# RePico.net
KiCad netlist of a schematic drawn in EAGLE
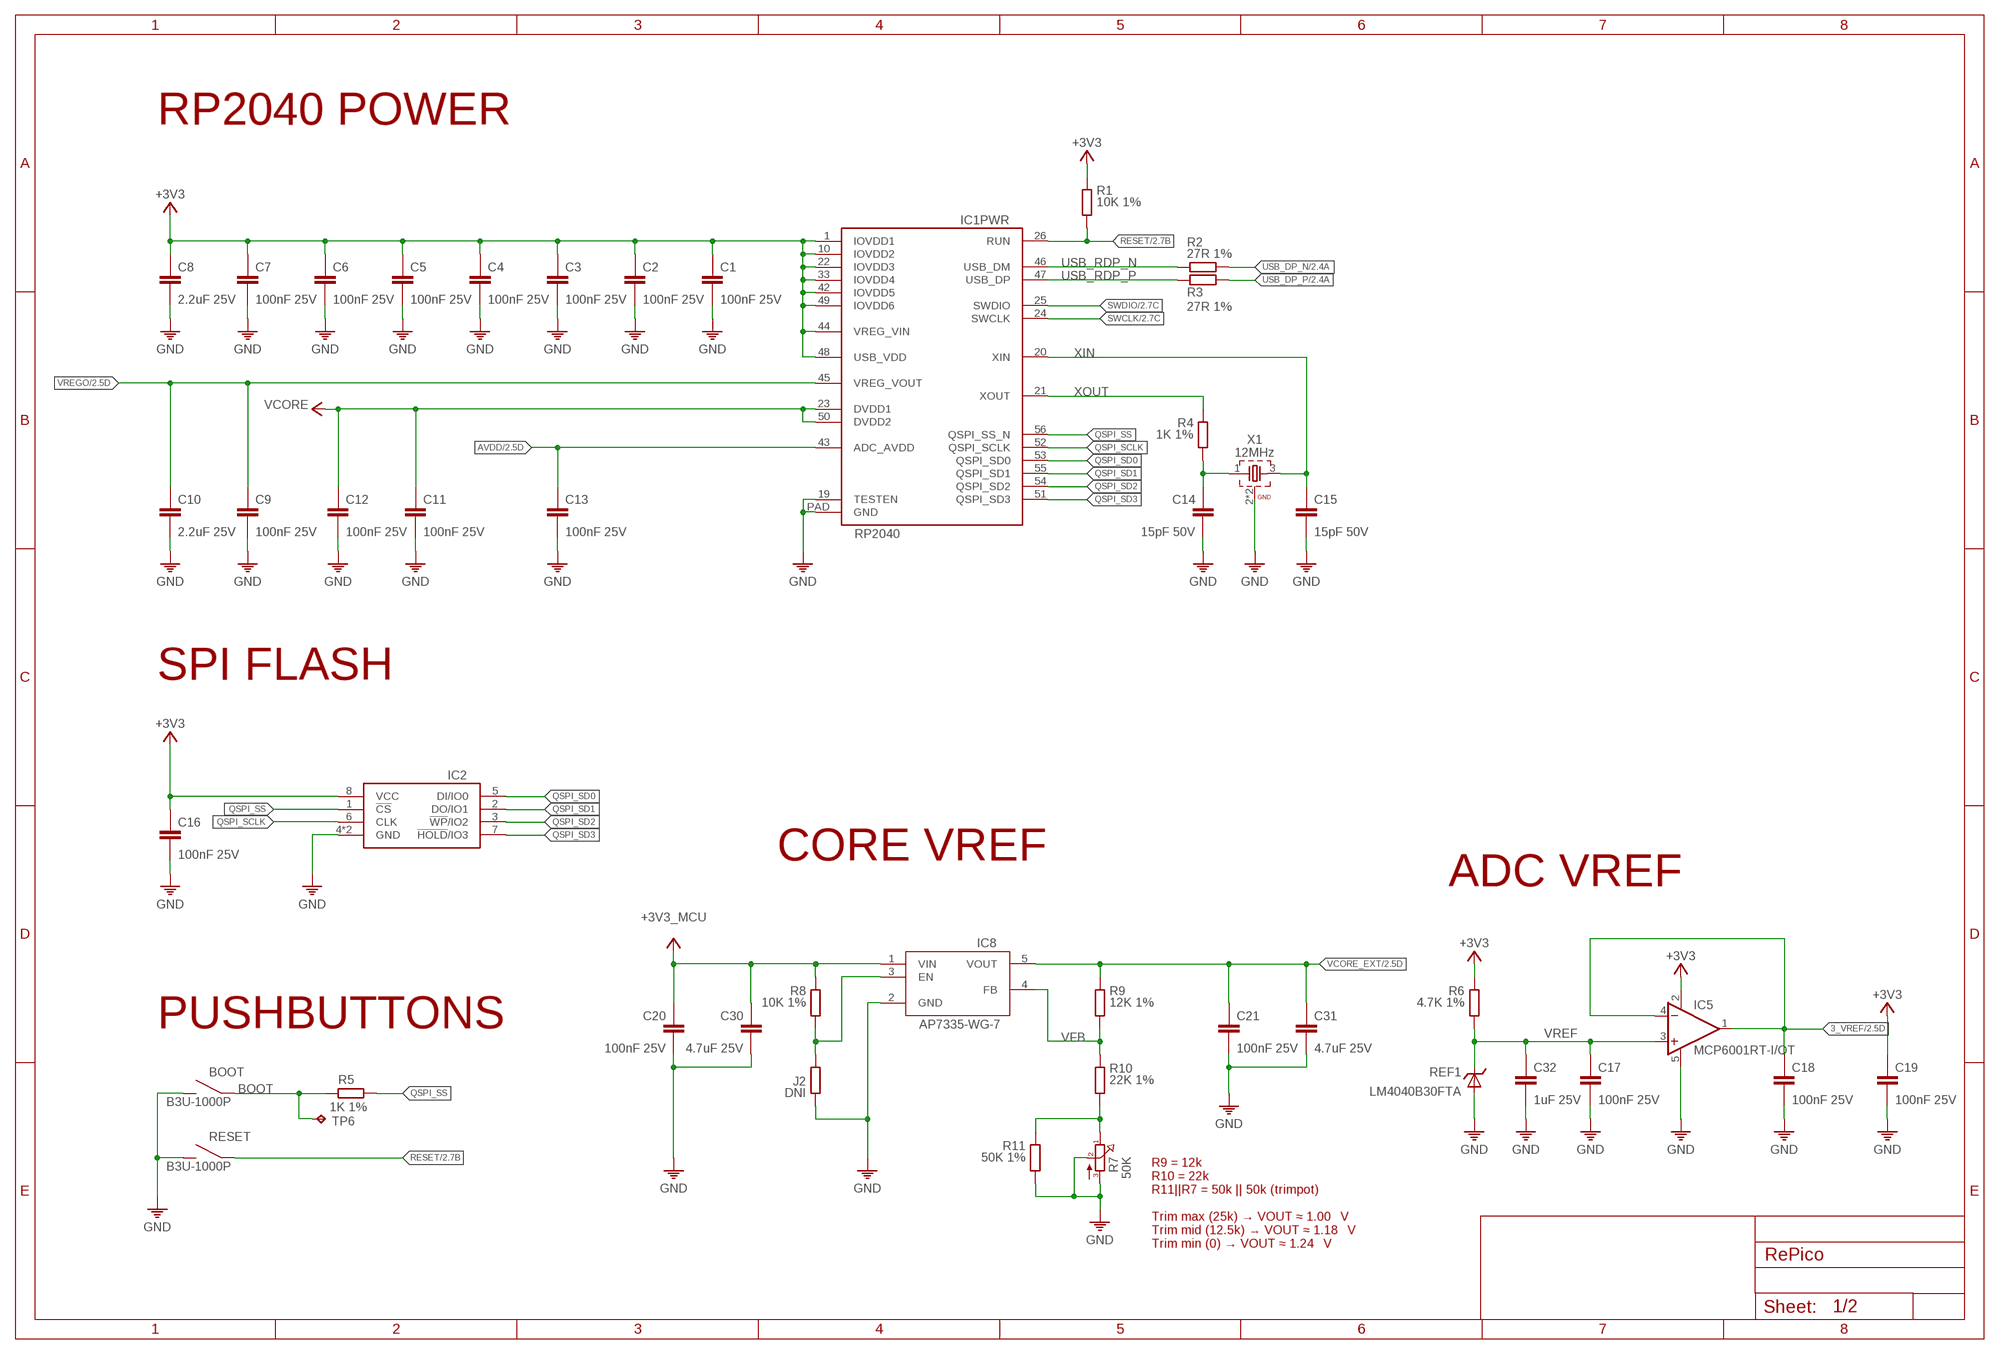
[diagram p0: schematic, sheet 1]
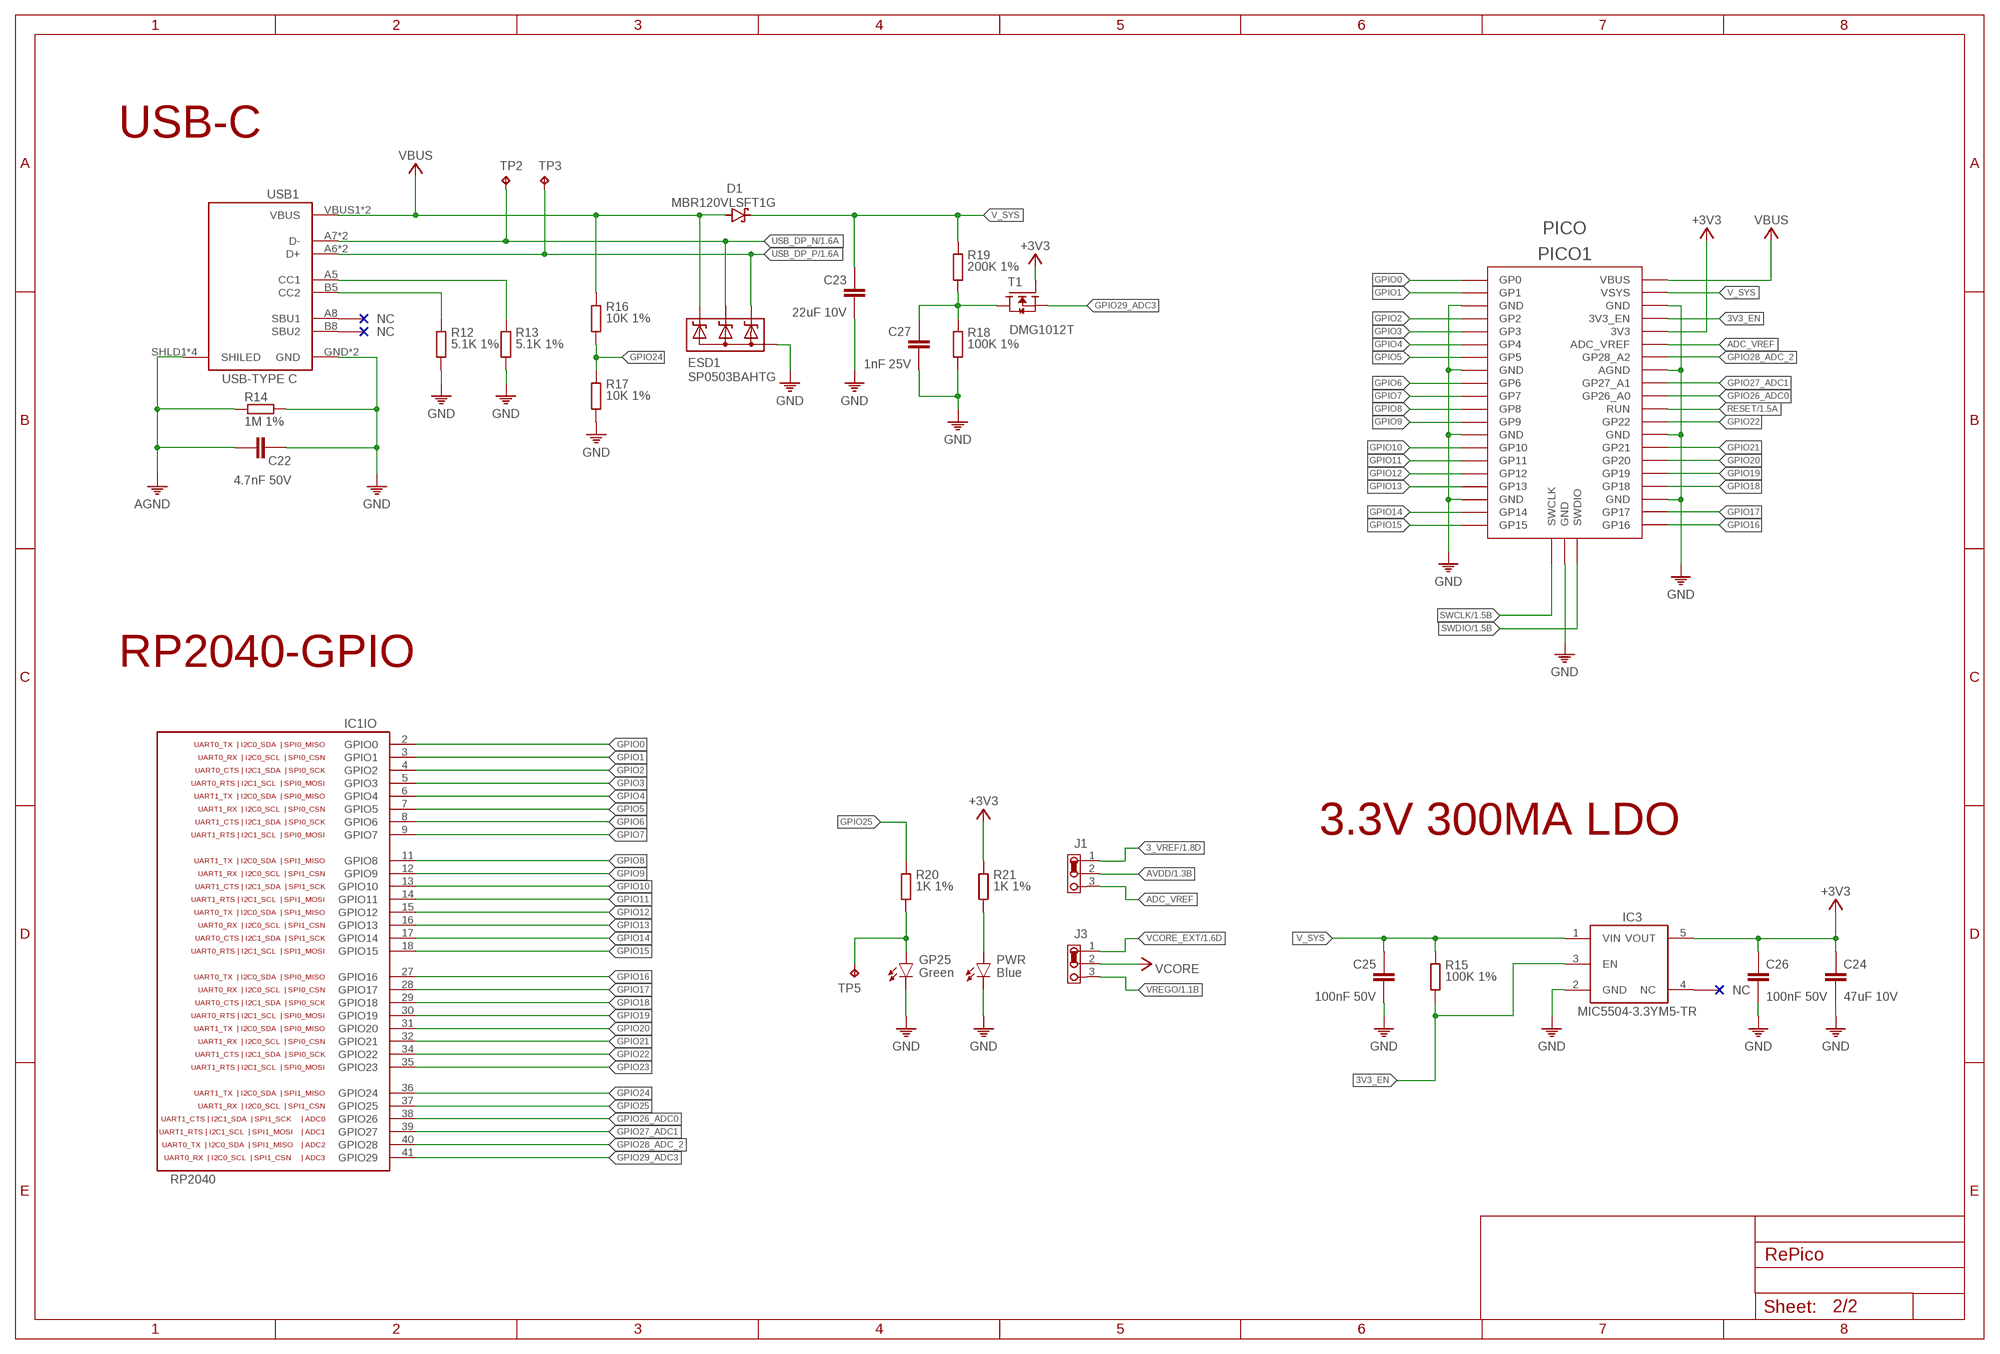
[diagram p1: schematic, sheet 2]

(export (version "E")
  (design (tool "Eeschema 10.0.6"))
  (components
    (comp (ref "BOOT")
      (value "B3U-1000P")
      (footprint "eagle-import:B3U-1000P")
      (fields (field (name "LCSC_PART") "C231329"))
      (libsource (lib "eagle-import") (part "B3U-1000P"))
    )
    (comp (ref "C1")
      (value "100nF 25V")
      (footprint "eagle-import:0201")
      (fields (field (name "LCSC_PART") "C76939"))
      (libsource (lib "eagle-import") (part "100NF-25V-0201"))
    )
    (comp (ref "C2")
      (value "100nF 25V")
      (footprint "eagle-import:0201")
      (fields (field (name "LCSC_PART") "C76939"))
      (libsource (lib "eagle-import") (part "100NF-25V-0201"))
    )
    (comp (ref "C3")
      (value "100nF 25V")
      (footprint "eagle-import:0201")
      (fields (field (name "LCSC_PART") "C76939"))
      (libsource (lib "eagle-import") (part "100NF-25V-0201"))
    )
    (comp (ref "C4")
      (value "100nF 25V")
      (footprint "eagle-import:0201")
      (fields (field (name "LCSC_PART") "C76939"))
      (libsource (lib "eagle-import") (part "100NF-25V-0201"))
    )
    (comp (ref "C5")
      (value "100nF 25V")
      (footprint "eagle-import:0201")
      (fields (field (name "LCSC_PART") "C76939"))
      (libsource (lib "eagle-import") (part "100NF-25V-0201"))
    )
    (comp (ref "C6")
      (value "100nF 25V")
      (footprint "eagle-import:0201")
      (fields (field (name "LCSC_PART") "C76939"))
      (libsource (lib "eagle-import") (part "100NF-25V-0201"))
    )
    (comp (ref "C7")
      (value "100nF 25V")
      (footprint "eagle-import:0201")
      (fields (field (name "LCSC_PART") "C76939"))
      (libsource (lib "eagle-import") (part "100NF-25V-0201"))
    )
    (comp (ref "C8")
      (value "2.2uF 25V")
      (footprint "eagle-import:0402")
      (fields (field (name "LCSC_PART") "C385032"))
      (libsource (lib "eagle-import") (part "2.2UF-25V0402"))
    )
    (comp (ref "C9")
      (value "100nF 25V")
      (footprint "eagle-import:0201")
      (fields (field (name "LCSC_PART") "C76939"))
      (libsource (lib "eagle-import") (part "100NF-25V-0201"))
    )
    (comp (ref "C10")
      (value "2.2uF 25V")
      (footprint "eagle-import:0402")
      (fields (field (name "LCSC_PART") "C385032"))
      (libsource (lib "eagle-import") (part "2.2UF-25V0402"))
    )
    (comp (ref "C11")
      (value "100nF 25V")
      (footprint "eagle-import:0201")
      (fields (field (name "LCSC_PART") "C76939"))
      (libsource (lib "eagle-import") (part "100NF-25V-0201"))
    )
    (comp (ref "C12")
      (value "100nF 25V")
      (footprint "eagle-import:0201")
      (fields (field (name "LCSC_PART") "C76939"))
      (libsource (lib "eagle-import") (part "100NF-25V-0201"))
    )
    (comp (ref "C13")
      (value "100nF 25V")
      (footprint "eagle-import:0201")
      (fields (field (name "LCSC_PART") "C76939"))
      (libsource (lib "eagle-import") (part "100NF-25V-0201"))
    )
    (comp (ref "C14")
      (value "15pF 50V")
      (footprint "eagle-import:0201")
      (fields (field (name "LCSC_PART") "C22374851"))
      (libsource (lib "eagle-import") (part "15PF-50V0201"))
    )
    (comp (ref "C15")
      (value "15pF 50V")
      (footprint "eagle-import:0201")
      (fields (field (name "LCSC_PART") "C22374851"))
      (libsource (lib "eagle-import") (part "15PF-50V0201"))
    )
    (comp (ref "C16")
      (value "100nF 25V")
      (footprint "eagle-import:0201")
      (fields (field (name "LCSC_PART") "C76939"))
      (libsource (lib "eagle-import") (part "100NF-25V-0201"))
    )
    (comp (ref "C17")
      (value "100nF 25V")
      (footprint "eagle-import:0201")
      (fields (field (name "LCSC_PART") "C76939"))
      (libsource (lib "eagle-import") (part "100NF-25V-0201"))
    )
    (comp (ref "C18")
      (value "100nF 25V")
      (footprint "eagle-import:0201")
      (fields (field (name "LCSC_PART") "C76939"))
      (libsource (lib "eagle-import") (part "100NF-25V-0201"))
    )
    (comp (ref "C19")
      (value "100nF 25V")
      (footprint "eagle-import:0201")
      (fields (field (name "LCSC_PART") "C76939"))
      (libsource (lib "eagle-import") (part "100NF-25V-0201"))
    )
    (comp (ref "C20")
      (value "100nF 25V")
      (footprint "eagle-import:0201")
      (fields (field (name "LCSC_PART") "C76939"))
      (libsource (lib "eagle-import") (part "100NF-25V-0201"))
    )
    (comp (ref "C21")
      (value "100nF 25V")
      (footprint "eagle-import:0201")
      (fields (field (name "LCSC_PART") "C76939"))
      (libsource (lib "eagle-import") (part "100NF-25V-0201"))
    )
    (comp (ref "C30")
      (value "4.7uF 25V")
      (footprint "eagle-import:0402")
      (fields (field (name "LCSC_PART") "C22367824"))
      (libsource (lib "eagle-import") (part "4.7UF-25V0402"))
    )
    (comp (ref "C31")
      (value "4.7uF 25V")
      (footprint "eagle-import:0402")
      (fields (field (name "LCSC_PART") "C22367824"))
      (libsource (lib "eagle-import") (part "4.7UF-25V0402"))
    )
    (comp (ref "C32")
      (value "1uF 25V")
      (footprint "eagle-import:0402")
      (fields (field (name "LCSC_PART") "C52923"))
      (libsource (lib "eagle-import") (part "1UF-25V0402"))
    )
    (comp (ref "IC1")
      (value "RP2040")
      (footprint "eagle-import:QFN56")
      (fields (field (name "LCSC_PART") "C2040"))
      (libsource (lib "eagle-import") (part "RP-2040"))
    )
    (comp (ref "IC2")
      (value "W25Q128JVP")
      (footprint "eagle-import:SON127P600X500X75-8N")
      (libsource (lib "eagle-import") (part "W25Q128JVP"))
    )
    (comp (ref "IC5")
      (value "MCP6001RT-I/OT")
      (footprint "eagle-import:SOT23-5")
      (fields (field (name "LCSC_PART") "C154973"))
      (libsource (lib "eagle-import") (part "MCP6001RT"))
    )
    (comp (ref "IC8")
      (value "AP7335-WG-7")
      (footprint "eagle-import:SOT23-5")
      (fields (field (name "LCSC_PART") "C460382"))
      (libsource (lib "eagle-import") (part "AP7335-WG-7"))
    )
    (comp (ref "J2")
      (value "DNI")
      (footprint "eagle-import:R0201")
      (libsource (lib "eagle-import") (part "R0201"))
    )
    (comp (ref "R1")
      (value "10K 1%")
      (footprint "eagle-import:0201")
      (fields (field (name "LCSC_PART") "C473048"))
      (libsource (lib "eagle-import") (part "10K-1%0201"))
    )
    (comp (ref "R2")
      (value "27R 1%")
      (footprint "eagle-import:0201")
      (fields (field (name "LCSC_PART") "C473051"))
      (libsource (lib "eagle-import") (part "27R-1%0201"))
    )
    (comp (ref "R3")
      (value "27R 1%")
      (footprint "eagle-import:0201")
      (fields (field (name "LCSC_PART") "C473051"))
      (libsource (lib "eagle-import") (part "27R-1%0201"))
    )
    (comp (ref "R4")
      (value "1K 1%")
      (footprint "eagle-import:0201")
      (fields (field (name "LCSC_PART") "C270365"))
      (libsource (lib "eagle-import") (part "1K-1%0201"))
    )
    (comp (ref "R5")
      (value "1K 1%")
      (footprint "eagle-import:0201")
      (fields (field (name "LCSC_PART") "C270365"))
      (libsource (lib "eagle-import") (part "1K-1%0201"))
    )
    (comp (ref "R6")
      (value "4.7K 1%")
      (footprint "eagle-import:0402")
      (fields (field (name "LCSC_PART") "C25900"))
      (libsource (lib "eagle-import") (part "4.7K-1%0402"))
    )
    (comp (ref "R7")
      (value "50K")
      (footprint "eagle-import:SMD_TRIMM")
      (fields (field (name "LCSC_PART") "C913246"))
      (libsource (lib "eagle-import") (part "TRIM-3X3.6-TC33X-2-503E"))
    )
    (comp (ref "R8")
      (value "10K 1%")
      (footprint "eagle-import:0201")
      (fields (field (name "LCSC_PART") "C473048"))
      (libsource (lib "eagle-import") (part "10K-1%0201"))
    )
    (comp (ref "R9")
      (value "12K 1%")
      (footprint "eagle-import:0201")
      (fields (field (name "LCSC_PART") "C270363"))
      (libsource (lib "eagle-import") (part "12K-1%0201"))
    )
    (comp (ref "R10")
      (value "22K 1%")
      (footprint "eagle-import:0201")
      (fields (field (name "LCSC_PART") "C474416"))
      (libsource (lib "eagle-import") (part "22K-1%0201"))
    )
    (comp (ref "R11")
      (value "50K 1%")
      (footprint "eagle-import:0402")
      (fields (field (name "LCSC_PART") "C166559"))
      (libsource (lib "eagle-import") (part "50K-1%0402"))
    )
    (comp (ref "REF1")
      (value "LM4040B30FTA")
      (footprint "eagle-import:SOT23")
      (fields (field (name "LCSC_PART") "C460604"))
      (libsource (lib "eagle-import") (part "LM4040BXX"))
    )
    (comp (ref "RESET")
      (value "B3U-1000P")
      (footprint "eagle-import:B3U-1000P")
      (fields (field (name "LCSC_PART") "C231329"))
      (libsource (lib "eagle-import") (part "B3U-1000P"))
    )
    (comp (ref "TP6")
      (value "TPB1,27")
      (footprint "eagle-import:B1,27")
      (libsource (lib "eagle-import") (part "TPB1,27"))
    )
    (comp (ref "X1")
      (value "12MHz")
      (footprint "eagle-import:WE-XTAL_CFPX-180")
      (fields (field (name "LCSC_PART") "C9002"))
      (libsource (lib "eagle-import") (part "CRYSTAL-3225X322512MSB4SI"))
    )
    (comp (ref "C22")
      (value "4.7nF 50V")
      (footprint "eagle-import:0603")
      (fields (field (name "LCSC_PART") "C53987"))
      (libsource (lib "eagle-import") (part "4.7NF-50V0603"))
    )
    (comp (ref "C23")
      (value "22uF 10V")
      (footprint "eagle-import:0603")
      (fields (field (name "LCSC_PART") "C60077"))
      (libsource (lib "eagle-import") (part "22UF-10V-0603"))
    )
    (comp (ref "C24")
      (value "47uF 10V")
      (footprint "eagle-import:0805")
      (fields (field (name "LCSC_PART") "C6119904"))
      (libsource (lib "eagle-import") (part "47UF-10V0805"))
    )
    (comp (ref "C25")
      (value "100nF 50V")
      (footprint "eagle-import:0402")
      (fields (field (name "LCSC_PART") "C307331"))
      (libsource (lib "eagle-import") (part "100NF-50V-0402"))
    )
    (comp (ref "C26")
      (value "100nF 50V")
      (footprint "eagle-import:0402")
      (fields (field (name "LCSC_PART") "C307331"))
      (libsource (lib "eagle-import") (part "100NF-50V-0402"))
    )
    (comp (ref "C27")
      (value "1nF 25V")
      (footprint "eagle-import:0201")
      (fields (field (name "LCSC_PART") "C7694325V"))
      (libsource (lib "eagle-import") (part "1NF-25V-0201"))
    )
    (comp (ref "D1")
      (value "MBR120VLSFT1G")
      (footprint "eagle-import:SOD-123")
      (fields (field (name "LCSC_PART") "C223608"))
      (libsource (lib "eagle-import") (part "MBR120VLSFT1G"))
    )
    (comp (ref "ESD1")
      (value "SP0503BAHTG")
      (footprint "eagle-import:SOT143")
      (fields (field (name "LCSC_PART") "C3040626"))
      (libsource (lib "eagle-import") (part "SP0503BAHT"))
    )
    (comp (ref "GP25")
      (value "Green")
      (footprint "eagle-import:LED-0603")
      (fields (field (name "LCSC_PART") "C965804"))
      (libsource (lib "eagle-import") (part "LED-GREENLED-0603"))
    )
    (comp (ref "IC3")
      (value "MIC5504-3.3YM5")
      (footprint "eagle-import:SOT23-5")
      (fields (field (name "LCSC_PART") "C41348078"))
      (libsource (lib "eagle-import") (part "MIC5504-3.3YM5-TR"))
    )
    (comp (ref "J1")
      (value "JUMPER-3")
      (footprint "eagle-import:JUMPER-3")
      (libsource (lib "eagle-import") (part "JUMPER-3"))
    )
    (comp (ref "J3")
      (value "JUMPER-3")
      (footprint "eagle-import:JUMPER-3")
      (libsource (lib "eagle-import") (part "JUMPER-3"))
    )
    (comp (ref "PICO1")
      (value "PICO")
      (footprint "eagle-import:PICO")
      (libsource (lib "eagle-import") (part "PICO"))
    )
    (comp (ref "PWR")
      (value "Blue")
      (footprint "eagle-import:LED-0603")
      (fields (field (name "LCSC_PART") "C965807"))
      (libsource (lib "eagle-import") (part "LED-BLUELED-0603"))
    )
    (comp (ref "R12")
      (value "5.1K 1%")
      (footprint "eagle-import:0201")
      (fields (field (name "LCSC_PART") "C274341"))
      (libsource (lib "eagle-import") (part "5.1K-1%0201"))
    )
    (comp (ref "R13")
      (value "5.1K 1%")
      (footprint "eagle-import:0201")
      (fields (field (name "LCSC_PART") "C274341"))
      (libsource (lib "eagle-import") (part "5.1K-1%0201"))
    )
    (comp (ref "R14")
      (value "1M 1%")
      (footprint "eagle-import:0603")
      (fields (field (name "LCSC_PART") "C22935"))
      (libsource (lib "eagle-import") (part "1M-1%0603"))
    )
    (comp (ref "R15")
      (value "100K 1%")
      (footprint "eagle-import:0201")
      (fields (field (name "LCSC_PART") "C270364"))
      (libsource (lib "eagle-import") (part "100K-1%0201"))
    )
    (comp (ref "R16")
      (value "10K 1%")
      (footprint "eagle-import:0201")
      (fields (field (name "LCSC_PART") "C473048"))
      (libsource (lib "eagle-import") (part "10K-1%0201"))
    )
    (comp (ref "R17")
      (value "10K 1%")
      (footprint "eagle-import:0201")
      (fields (field (name "LCSC_PART") "C473048"))
      (libsource (lib "eagle-import") (part "10K-1%0201"))
    )
    (comp (ref "R18")
      (value "100K 1%")
      (footprint "eagle-import:0201")
      (fields (field (name "LCSC_PART") "C270364"))
      (libsource (lib "eagle-import") (part "100K-1%0201"))
    )
    (comp (ref "R19")
      (value "200K 1%")
      (footprint "eagle-import:0201")
      (fields (field (name "LCSC_PART") "C270357"))
      (libsource (lib "eagle-import") (part "200K-1%0201"))
    )
    (comp (ref "R20")
      (value "1K 1%")
      (footprint "eagle-import:0402")
      (fields (field (name "LCSC_PART") "C11702"))
      (libsource (lib "eagle-import") (part "1K-1%0402"))
    )
    (comp (ref "R21")
      (value "1K 1%")
      (footprint "eagle-import:0402")
      (fields (field (name "LCSC_PART") "C11702"))
      (libsource (lib "eagle-import") (part "1K-1%0402"))
    )
    (comp (ref "T1")
      (value "DMG1012T")
      (footprint "eagle-import:SOT23")
      (fields (field (name "LCSC_PART") "C2830301"))
      (libsource (lib "eagle-import") (part "DMG1012T"))
    )
    (comp (ref "TP2")
      (value "TPB1,27")
      (footprint "eagle-import:B1,27")
      (libsource (lib "eagle-import") (part "TPB1,27"))
    )
    (comp (ref "TP3")
      (value "TPB1,27")
      (footprint "eagle-import:B1,27")
      (libsource (lib "eagle-import") (part "TPB1,27"))
    )
    (comp (ref "TP5")
      (value "TPB1,27")
      (footprint "eagle-import:B1,27")
      (libsource (lib "eagle-import") (part "TPB1,27"))
    )
    (comp (ref "USB1")
      (value "USB-TYPE-C-018")
      (footprint "eagle-import:USB-C")
      (fields (field (name "LCSC_PART") "C2927038"))
      (libsource (lib "eagle-import") (part "USB_C-THT"))
    )
  )
  (nets
    (net (code "1") (name "+3V3") (class "Default")
      (node (ref "C1") (pin "1") (pinfunction "1_1") (pintype "passive"))
      (node (ref "C16") (pin "1") (pinfunction "1_1") (pintype "passive"))
      (node (ref "C19") (pin "1") (pinfunction "1_1") (pintype "passive"))
      (node (ref "C2") (pin "1") (pinfunction "1_1") (pintype "passive"))
      (node (ref "C24") (pin "1") (pinfunction "1_1") (pintype "passive"))
      (node (ref "C26") (pin "1") (pinfunction "1_1") (pintype "passive"))
      (node (ref "C3") (pin "1") (pinfunction "1_1") (pintype "passive"))
      (node (ref "C4") (pin "1") (pinfunction "1_1") (pintype "passive"))
      (node (ref "C5") (pin "1") (pinfunction "1_1") (pintype "passive"))
      (node (ref "C6") (pin "1") (pinfunction "1_1") (pintype "passive"))
      (node (ref "C7") (pin "1") (pinfunction "1_1") (pintype "passive"))
      (node (ref "C8") (pin "1") (pinfunction "1_1") (pintype "passive"))
      (node (ref "IC1") (pin "1") (pinfunction "IOVDD1_1") (pintype "power_in"))
      (node (ref "IC1") (pin "10") (pinfunction "IOVDD2_10") (pintype "power_in"))
      (node (ref "IC1") (pin "22") (pinfunction "IOVDD3_22") (pintype "power_in"))
      (node (ref "IC1") (pin "33") (pinfunction "IOVDD4_33") (pintype "power_in"))
      (node (ref "IC1") (pin "42") (pinfunction "IOVDD5_42") (pintype "power_in"))
      (node (ref "IC1") (pin "44") (pinfunction "VREG_VIN_44") (pintype "power_in"))
      (node (ref "IC1") (pin "48") (pinfunction "USB_VDD_48") (pintype "power_in"))
      (node (ref "IC1") (pin "49") (pinfunction "IOVDD6_49") (pintype "power_in"))
      (node (ref "IC2") (pin "8") (pinfunction "VCC_8") (pintype "power_in"))
      (node (ref "IC3") (pin "5") (pinfunction "VOUT_5") (pintype "bidirectional"))
      (node (ref "IC5") (pin "2") (pinfunction "V+_2") (pintype "power_in"))
      (node (ref "PICO1") (pin "3V") (pinfunction "3V3_3V") (pintype "bidirectional"))
      (node (ref "PICO1") (pin "3V3") (pinfunction "3V3_3V3") (pintype "bidirectional"))
      (node (ref "R1") (pin "1") (pinfunction "1_1") (pintype "passive"))
      (node (ref "R21") (pin "1") (pinfunction "1_1") (pintype "passive"))
      (node (ref "R6") (pin "1") (pinfunction "1_1") (pintype "passive"))
      (node (ref "T1") (pin "1") (pinfunction "G_1") (pintype "passive"))
    )
    (net (code "2") (name "+3V3_MCU") (class "Default")
      (node (ref "C20") (pin "1") (pinfunction "1_1") (pintype "passive"))
      (node (ref "C30") (pin "1") (pinfunction "1_1") (pintype "passive"))
      (node (ref "IC8") (pin "1") (pinfunction "VIN_1") (pintype "power_in"))
      (node (ref "R8") (pin "1") (pinfunction "1_1") (pintype "passive"))
    )
    (net (code "3") (name "3V3_EN") (class "Default")
      (node (ref "IC3") (pin "3") (pinfunction "EN_3") (pintype "bidirectional"))
      (node (ref "PICO1") (pin "3V3_EN") (pinfunction "3V3_EN_3V3_EN") (pintype "bidirectional"))
      (node (ref "PICO1") (pin "3VE") (pinfunction "3V3_EN_3VE") (pintype "bidirectional"))
      (node (ref "R15") (pin "2") (pinfunction "2_2") (pintype "passive"))
    )
    (net (code "4") (name "3_VREF") (class "Default")
      (node (ref "C18") (pin "1") (pinfunction "1_1") (pintype "passive"))
      (node (ref "IC5") (pin "1") (pinfunction "OUT_1") (pintype "output"))
      (node (ref "IC5") (pin "4") (pinfunction "-IN_4") (pintype "input"))
      (node (ref "J1") (pin "1") (pinfunction "1_1") (pintype "bidirectional"))
    )
    (net (code "5") (name "ADC_VREF") (class "Default")
      (node (ref "J1") (pin "3") (pinfunction "3_3") (pintype "bidirectional"))
      (node (ref "PICO1") (pin "ADC_VREF") (pinfunction "ADC_VREF_ADC_VREF") (pintype "bidirectional"))
      (node (ref "PICO1") (pin "AVR") (pinfunction "ADC_VREF_AVR") (pintype "bidirectional"))
    )
    (net (code "6") (name "AGND") (class "Default")
      (node (ref "C22") (pin "1") (pinfunction "1_1") (pintype "passive"))
      (node (ref "R14") (pin "1") (pinfunction "1_1") (pintype "passive"))
      (node (ref "USB1") (pin "SHLD1") (pinfunction "SHILED_SHLD1") (pintype "power_in"))
      (node (ref "USB1") (pin "SHLD2") (pinfunction "SHILED_SHLD2") (pintype "power_in"))
      (node (ref "USB1") (pin "SHLD3") (pinfunction "SHILED_SHLD3") (pintype "power_in"))
      (node (ref "USB1") (pin "SHLD4") (pinfunction "SHILED_SHLD4") (pintype "power_in"))
    )
    (net (code "7") (name "AVDD") (class "Default")
      (node (ref "C13") (pin "1") (pinfunction "1_1") (pintype "passive"))
      (node (ref "IC1") (pin "43") (pinfunction "ADC_AVDD_43") (pintype "power_in"))
      (node (ref "J1") (pin "2") (pinfunction "2_2") (pintype "bidirectional"))
    )
    (net (code "8") (name "BOOT") (class "Default")
      (node (ref "BOOT") (pin "1") (pinfunction "P$1_1") (pintype "bidirectional"))
      (node (ref "R5") (pin "1") (pinfunction "1_1") (pintype "passive"))
      (node (ref "TP6") (pin "TP") (pinfunction "TP_TP") (pintype "input"))
    )
    (net (code "9") (name "GND") (class "Default")
      (node (ref "BOOT") (pin "2") (pinfunction "P$2_2") (pintype "bidirectional"))
      (node (ref "C1") (pin "2") (pinfunction "2_2") (pintype "passive"))
      (node (ref "C10") (pin "2") (pinfunction "2_2") (pintype "passive"))
      (node (ref "C11") (pin "2") (pinfunction "2_2") (pintype "passive"))
      (node (ref "C12") (pin "2") (pinfunction "2_2") (pintype "passive"))
      (node (ref "C13") (pin "2") (pinfunction "2_2") (pintype "passive"))
      (node (ref "C14") (pin "2") (pinfunction "2_2") (pintype "passive"))
      (node (ref "C15") (pin "2") (pinfunction "2_2") (pintype "passive"))
      (node (ref "C16") (pin "2") (pinfunction "2_2") (pintype "passive"))
      (node (ref "C17") (pin "2") (pinfunction "2_2") (pintype "passive"))
      (node (ref "C18") (pin "2") (pinfunction "2_2") (pintype "passive"))
      (node (ref "C19") (pin "2") (pinfunction "2_2") (pintype "passive"))
      (node (ref "C2") (pin "2") (pinfunction "2_2") (pintype "passive"))
      (node (ref "C20") (pin "2") (pinfunction "2_2") (pintype "passive"))
      (node (ref "C21") (pin "2") (pinfunction "2_2") (pintype "passive"))
      (node (ref "C22") (pin "2") (pinfunction "2_2") (pintype "passive"))
      (node (ref "C23") (pin "2") (pinfunction "2_2") (pintype "passive"))
      (node (ref "C24") (pin "2") (pinfunction "2_2") (pintype "passive"))
      (node (ref "C25") (pin "2") (pinfunction "2_2") (pintype "passive"))
      (node (ref "C26") (pin "2") (pinfunction "2_2") (pintype "passive"))
      (node (ref "C27") (pin "2") (pinfunction "2_2") (pintype "passive"))
      (node (ref "C3") (pin "2") (pinfunction "2_2") (pintype "passive"))
      (node (ref "C30") (pin "2") (pinfunction "2_2") (pintype "passive"))
      (node (ref "C31") (pin "2") (pinfunction "2_2") (pintype "passive"))
      (node (ref "C32") (pin "2") (pinfunction "2_2") (pintype "passive"))
      (node (ref "C4") (pin "2") (pinfunction "2_2") (pintype "passive"))
      (node (ref "C5") (pin "2") (pinfunction "2_2") (pintype "passive"))
      (node (ref "C6") (pin "2") (pinfunction "2_2") (pintype "passive"))
      (node (ref "C7") (pin "2") (pinfunction "2_2") (pintype "passive"))
      (node (ref "C8") (pin "2") (pinfunction "2_2") (pintype "passive"))
      (node (ref "C9") (pin "2") (pinfunction "2_2") (pintype "passive"))
      (node (ref "ESD1") (pin "1") (pinfunction "A_1") (pintype "bidirectional"))
      (node (ref "GP25") (pin "C") (pinfunction "C_C") (pintype "passive"))
      (node (ref "IC1") (pin "19") (pinfunction "TESTEN_19") (pintype "bidirectional"))
      (node (ref "IC1") (pin "PAD") (pinfunction "GND_PAD") (pintype "power_in"))
      (node (ref "IC2") (pin "4") (pinfunction "GND_4") (pintype "power_in"))
      (node (ref "IC2") (pin "PAD") (pinfunction "GND_PAD") (pintype "power_in"))
      (node (ref "IC3") (pin "2") (pinfunction "GND_2") (pintype "bidirectional"))
      (node (ref "IC5") (pin "5") (pinfunction "V-_5") (pintype "power_in"))
      (node (ref "IC8") (pin "2") (pinfunction "GND_2") (pintype "power_in"))
      (node (ref "J2") (pin "2") (pinfunction "2_2") (pintype "passive"))
      (node (ref "PICO1") (pin "AGN") (pinfunction "AGND_AGN") (pintype "bidirectional"))
      (node (ref "PICO1") (pin "AGND") (pinfunction "AGND_AGND") (pintype "bidirectional"))
      (node (ref "PICO1") (pin "G@1") (pinfunction "GND_G@1") (pintype "bidirectional"))
      (node (ref "PICO1") (pin "G@2") (pinfunction "GND_G@2") (pintype "bidirectional"))
      (node (ref "PICO1") (pin "G@3") (pinfunction "GND_G@3") (pintype "bidirectional"))
      (node (ref "PICO1") (pin "G@4") (pinfunction "GND_G@4") (pintype "bidirectional"))
      (node (ref "PICO1") (pin "G@5") (pinfunction "GND_G@5") (pintype "bidirectional"))
      (node (ref "PICO1") (pin "G@6") (pinfunction "GND_G@6") (pintype "bidirectional"))
      (node (ref "PICO1") (pin "G@7") (pinfunction "GND_G@7") (pintype "bidirectional"))
      (node (ref "PICO1") (pin "G@8") (pinfunction "GND_G@8") (pintype "bidirectional"))
      (node (ref "PICO1") (pin "GND@1") (pinfunction "GND_GND@1") (pintype "bidirectional"))
      (node (ref "PICO1") (pin "GND@2") (pinfunction "GND_GND@2") (pintype "bidirectional"))
      (node (ref "PICO1") (pin "GND@3") (pinfunction "GND_GND@3") (pintype "bidirectional"))
      (node (ref "PICO1") (pin "GND@4") (pinfunction "GND_GND@4") (pintype "bidirectional"))
      (node (ref "PICO1") (pin "GND@5") (pinfunction "GND_GND@5") (pintype "bidirectional"))
      (node (ref "PICO1") (pin "GND@6") (pinfunction "GND_GND@6") (pintype "bidirectional"))
      (node (ref "PICO1") (pin "GND@7") (pinfunction "GND_GND@7") (pintype "bidirectional"))
      (node (ref "PICO1") (pin "GND@8") (pinfunction "GND_GND@8") (pintype "bidirectional"))
      (node (ref "PWR") (pin "C") (pinfunction "C_C") (pintype "passive"))
      (node (ref "R11") (pin "2") (pinfunction "2_2") (pintype "passive"))
      (node (ref "R12") (pin "2") (pinfunction "2_2") (pintype "passive"))
      (node (ref "R13") (pin "2") (pinfunction "2_2") (pintype "passive"))
      (node (ref "R14") (pin "2") (pinfunction "2_2") (pintype "passive"))
      (node (ref "R17") (pin "2") (pinfunction "2_2") (pintype "passive"))
      (node (ref "R18") (pin "2") (pinfunction "2_2") (pintype "passive"))
      (node (ref "R7") (pin "2") (pinfunction "2_2") (pintype "passive"))
      (node (ref "R7") (pin "3") (pinfunction "3_3") (pintype "passive"))
      (node (ref "REF1") (pin "2") (pinfunction "A_2") (pintype "passive"))
      (node (ref "REF1") (pin "3") (pinfunction "A_3") (pintype "passive"))
      (node (ref "RESET") (pin "2") (pinfunction "P$2_2") (pintype "bidirectional"))
      (node (ref "USB1") (pin "GND") (pinfunction "GND_GND") (pintype "power_in"))
      (node (ref "USB1") (pin "GND2") (pinfunction "GND_GND2") (pintype "power_in"))
      (node (ref "X1") (pin "2") (pinfunction "GND_2") (pintype "passive"))
      (node (ref "X1") (pin "4") (pinfunction "GND_4") (pintype "passive"))
    )
    (net (code "10") (name "GPIO0") (class "Default")
      (node (ref "IC1") (pin "2") (pinfunction "GPIO0_2") (pintype "bidirectional"))
      (node (ref "PICO1") (pin "0") (pinfunction "GP0_0") (pintype "bidirectional"))
      (node (ref "PICO1") (pin "GP0") (pinfunction "GP0_GP0") (pintype "bidirectional"))
    )
    (net (code "11") (name "GPIO1") (class "Default")
      (node (ref "IC1") (pin "3") (pinfunction "GPIO1_3") (pintype "bidirectional"))
      (node (ref "PICO1") (pin "1") (pinfunction "GP1_1") (pintype "bidirectional"))
      (node (ref "PICO1") (pin "GP1") (pinfunction "GP1_GP1") (pintype "bidirectional"))
    )
    (net (code "12") (name "GPIO2") (class "Default")
      (node (ref "IC1") (pin "4") (pinfunction "GPIO2_4") (pintype "bidirectional"))
      (node (ref "PICO1") (pin "2") (pinfunction "GP2_2") (pintype "bidirectional"))
      (node (ref "PICO1") (pin "GP2") (pinfunction "GP2_GP2") (pintype "bidirectional"))
    )
    (net (code "13") (name "GPIO3") (class "Default")
      (node (ref "IC1") (pin "5") (pinfunction "GPIO3_5") (pintype "bidirectional"))
      (node (ref "PICO1") (pin "3") (pinfunction "GP3_3") (pintype "bidirectional"))
      (node (ref "PICO1") (pin "GP3") (pinfunction "GP3_GP3") (pintype "bidirectional"))
    )
    (net (code "14") (name "GPIO4") (class "Default")
      (node (ref "IC1") (pin "6") (pinfunction "GPIO4_6") (pintype "bidirectional"))
      (node (ref "PICO1") (pin "4") (pinfunction "GP4_4") (pintype "bidirectional"))
      (node (ref "PICO1") (pin "GP4") (pinfunction "GP4_GP4") (pintype "bidirectional"))
    )
    (net (code "15") (name "GPIO5") (class "Default")
      (node (ref "IC1") (pin "7") (pinfunction "GPIO5_7") (pintype "bidirectional"))
      (node (ref "PICO1") (pin "5") (pinfunction "GP5_5") (pintype "bidirectional"))
      (node (ref "PICO1") (pin "GP5") (pinfunction "GP5_GP5") (pintype "bidirectional"))
    )
    (net (code "16") (name "GPIO6") (class "Default")
      (node (ref "IC1") (pin "8") (pinfunction "GPIO6_8") (pintype "bidirectional"))
      (node (ref "PICO1") (pin "6") (pinfunction "GP6_6") (pintype "bidirectional"))
      (node (ref "PICO1") (pin "GP6") (pinfunction "GP6_GP6") (pintype "bidirectional"))
    )
    (net (code "17") (name "GPIO7") (class "Default")
      (node (ref "IC1") (pin "9") (pinfunction "GPIO7_9") (pintype "bidirectional"))
      (node (ref "PICO1") (pin "7") (pinfunction "GP7_7") (pintype "bidirectional"))
      (node (ref "PICO1") (pin "GP7") (pinfunction "GP7_GP7") (pintype "bidirectional"))
    )
    (net (code "18") (name "GPIO8") (class "Default")
      (node (ref "IC1") (pin "11") (pinfunction "GPIO8_11") (pintype "bidirectional"))
      (node (ref "PICO1") (pin "8") (pinfunction "GP8_8") (pintype "bidirectional"))
      (node (ref "PICO1") (pin "GP8") (pinfunction "GP8_GP8") (pintype "bidirectional"))
    )
    (net (code "19") (name "GPIO9") (class "Default")
      (node (ref "IC1") (pin "12") (pinfunction "GPIO9_12") (pintype "bidirectional"))
      (node (ref "PICO1") (pin "9") (pinfunction "GP9_9") (pintype "bidirectional"))
      (node (ref "PICO1") (pin "GP9") (pinfunction "GP9_GP9") (pintype "bidirectional"))
    )
    (net (code "20") (name "GPIO10") (class "Default")
      (node (ref "IC1") (pin "13") (pinfunction "GPIO10_13") (pintype "bidirectional"))
      (node (ref "PICO1") (pin "10") (pinfunction "GP10_10") (pintype "bidirectional"))
      (node (ref "PICO1") (pin "GP10") (pinfunction "GP10_GP10") (pintype "bidirectional"))
    )
    (net (code "21") (name "GPIO11") (class "Default")
      (node (ref "IC1") (pin "14") (pinfunction "GPIO11_14") (pintype "bidirectional"))
      (node (ref "PICO1") (pin "11") (pinfunction "GP11_11") (pintype "bidirectional"))
      (node (ref "PICO1") (pin "GP11") (pinfunction "GP11_GP11") (pintype "bidirectional"))
    )
    (net (code "22") (name "GPIO12") (class "Default")
      (node (ref "IC1") (pin "15") (pinfunction "GPIO12_15") (pintype "bidirectional"))
      (node (ref "PICO1") (pin "12") (pinfunction "GP12_12") (pintype "bidirectional"))
      (node (ref "PICO1") (pin "GP12") (pinfunction "GP12_GP12") (pintype "bidirectional"))
    )
    (net (code "23") (name "GPIO13") (class "Default")
      (node (ref "IC1") (pin "16") (pinfunction "GPIO13_16") (pintype "bidirectional"))
      (node (ref "PICO1") (pin "13") (pinfunction "GP13_13") (pintype "bidirectional"))
      (node (ref "PICO1") (pin "GP13") (pinfunction "GP13_GP13") (pintype "bidirectional"))
    )
    (net (code "24") (name "GPIO14") (class "Default")
      (node (ref "IC1") (pin "17") (pinfunction "GPIO14_17") (pintype "bidirectional"))
      (node (ref "PICO1") (pin "14") (pinfunction "GP14_14") (pintype "bidirectional"))
      (node (ref "PICO1") (pin "GP14") (pinfunction "GP14_GP14") (pintype "bidirectional"))
    )
    (net (code "25") (name "GPIO15") (class "Default")
      (node (ref "IC1") (pin "18") (pinfunction "GPIO15_18") (pintype "bidirectional"))
      (node (ref "PICO1") (pin "15") (pinfunction "GP15_15") (pintype "bidirectional"))
      (node (ref "PICO1") (pin "GP15") (pinfunction "GP15_GP15") (pintype "bidirectional"))
    )
    (net (code "26") (name "GPIO16") (class "Default")
      (node (ref "IC1") (pin "27") (pinfunction "GPIO16_27") (pintype "bidirectional"))
      (node (ref "PICO1") (pin "16") (pinfunction "GP16_16") (pintype "bidirectional"))
      (node (ref "PICO1") (pin "GP16") (pinfunction "GP16_GP16") (pintype "bidirectional"))
    )
    (net (code "27") (name "GPIO17") (class "Default")
      (node (ref "IC1") (pin "28") (pinfunction "GPIO17_28") (pintype "bidirectional"))
      (node (ref "PICO1") (pin "17") (pinfunction "GP17_17") (pintype "bidirectional"))
      (node (ref "PICO1") (pin "GP17") (pinfunction "GP17_GP17") (pintype "bidirectional"))
    )
    (net (code "28") (name "GPIO18") (class "Default")
      (node (ref "IC1") (pin "29") (pinfunction "GPIO18_29") (pintype "bidirectional"))
      (node (ref "PICO1") (pin "18") (pinfunction "GP18_18") (pintype "bidirectional"))
      (node (ref "PICO1") (pin "GP18") (pinfunction "GP18_GP18") (pintype "bidirectional"))
    )
    (net (code "29") (name "GPIO19") (class "Default")
      (node (ref "IC1") (pin "30") (pinfunction "GPIO19_30") (pintype "bidirectional"))
      (node (ref "PICO1") (pin "19") (pinfunction "GP19_19") (pintype "bidirectional"))
      (node (ref "PICO1") (pin "GP19") (pinfunction "GP19_GP19") (pintype "bidirectional"))
    )
    (net (code "30") (name "GPIO20") (class "Default")
      (node (ref "IC1") (pin "31") (pinfunction "GPIO20_31") (pintype "bidirectional"))
      (node (ref "PICO1") (pin "20") (pinfunction "GP20_20") (pintype "bidirectional"))
      (node (ref "PICO1") (pin "GP20") (pinfunction "GP20_GP20") (pintype "bidirectional"))
    )
    (net (code "31") (name "GPIO21") (class "Default")
      (node (ref "IC1") (pin "32") (pinfunction "GPIO21_32") (pintype "bidirectional"))
      (node (ref "PICO1") (pin "21") (pinfunction "GP21_21") (pintype "bidirectional"))
      (node (ref "PICO1") (pin "GP21") (pinfunction "GP21_GP21") (pintype "bidirectional"))
    )
    (net (code "32") (name "GPIO22") (class "Default")
      (node (ref "IC1") (pin "34") (pinfunction "GPIO22_34") (pintype "bidirectional"))
      (node (ref "PICO1") (pin "22") (pinfunction "GP22_22") (pintype "bidirectional"))
      (node (ref "PICO1") (pin "GP22") (pinfunction "GP22_GP22") (pintype "bidirectional"))
    )
    (net (code "33") (name "GPIO23") (class "Default")
      (node (ref "IC1") (pin "35") (pinfunction "GPIO23_35") (pintype "bidirectional"))
    )
    (net (code "34") (name "GPIO24") (class "Default")
      (node (ref "IC1") (pin "36") (pinfunction "GPIO24_36") (pintype "bidirectional"))
      (node (ref "R16") (pin "2") (pinfunction "2_2") (pintype "passive"))
      (node (ref "R17") (pin "1") (pinfunction "1_1") (pintype "passive"))
    )
    (net (code "35") (name "GPIO25") (class "Default")
      (node (ref "IC1") (pin "37") (pinfunction "GPIO25_37") (pintype "bidirectional"))
      (node (ref "R20") (pin "1") (pinfunction "1_1") (pintype "passive"))
    )
    (net (code "36") (name "GPIO26_ADC0") (class "Default")
      (node (ref "IC1") (pin "38") (pinfunction "GPIO26_38") (pintype "bidirectional"))
      (node (ref "PICO1") (pin "26") (pinfunction "GP26_A0_26") (pintype "bidirectional"))
      (node (ref "PICO1") (pin "GP26_A0") (pinfunction "GP26_A0_GP26_A0") (pintype "bidirectional"))
    )
    (net (code "37") (name "GPIO27_ADC1") (class "Default")
      (node (ref "IC1") (pin "39") (pinfunction "GPIO27_39") (pintype "bidirectional"))
      (node (ref "PICO1") (pin "27") (pinfunction "GP27_A1_27") (pintype "bidirectional"))
      (node (ref "PICO1") (pin "GP27_A1") (pinfunction "GP27_A1_GP27_A1") (pintype "bidirectional"))
    )
    (net (code "38") (name "GPIO28_ADC_2") (class "Default")
      (node (ref "IC1") (pin "40") (pinfunction "GPIO28_40") (pintype "bidirectional"))
      (node (ref "PICO1") (pin "28") (pinfunction "GP28_A2_28") (pintype "bidirectional"))
      (node (ref "PICO1") (pin "GP28_A2") (pinfunction "GP28_A2_GP28_A2") (pintype "bidirectional"))
    )
    (net (code "39") (name "GPIO29_ADC3") (class "Default")
      (node (ref "IC1") (pin "41") (pinfunction "GPIO29_41") (pintype "bidirectional"))
      (node (ref "T1") (pin "2") (pinfunction "S_2") (pintype "passive"))
    )
    (net (code "40") (name "Net-(C14-Pad1)") (class "Default")
      (node (ref "C14") (pin "1") (pinfunction "1_1") (pintype "passive"))
      (node (ref "R4") (pin "2") (pinfunction "2_2") (pintype "passive"))
      (node (ref "X1") (pin "1") (pinfunction "1_1") (pintype "passive"))
    )
    (net (code "41") (name "Net-(GP25-PadA)") (class "Default")
      (node (ref "GP25") (pin "A") (pinfunction "A_A") (pintype "passive"))
      (node (ref "R20") (pin "2") (pinfunction "2_2") (pintype "passive"))
      (node (ref "TP5") (pin "TP") (pinfunction "TP_TP") (pintype "input"))
    )
    (net (code "42") (name "Net-(IC8-EN)") (class "Default")
      (node (ref "IC8") (pin "3") (pinfunction "EN_3") (pintype "input"))
      (node (ref "J2") (pin "1") (pinfunction "1_1") (pintype "passive"))
      (node (ref "R8") (pin "2") (pinfunction "2_2") (pintype "passive"))
    )
    (net (code "43") (name "Net-(PWR-PadA)") (class "Default")
      (node (ref "PWR") (pin "A") (pinfunction "A_A") (pintype "passive"))
      (node (ref "R21") (pin "2") (pinfunction "2_2") (pintype "passive"))
    )
    (net (code "44") (name "Net-(R10-Pad2)") (class "Default")
      (node (ref "R10") (pin "2") (pinfunction "2_2") (pintype "passive"))
      (node (ref "R11") (pin "1") (pinfunction "1_1") (pintype "passive"))
      (node (ref "R7") (pin "1") (pinfunction "1_1") (pintype "passive"))
    )
    (net (code "45") (name "Net-(T1-D)") (class "Default")
      (node (ref "C27") (pin "1") (pinfunction "1_1") (pintype "passive"))
      (node (ref "R18") (pin "1") (pinfunction "1_1") (pintype "passive"))
      (node (ref "R19") (pin "2") (pinfunction "2_2") (pintype "passive"))
      (node (ref "T1") (pin "3") (pinfunction "D_3") (pintype "passive"))
    )
    (net (code "46") (name "Net-(USB1-CC1)") (class "Default")
      (node (ref "R13") (pin "1") (pinfunction "1_1") (pintype "passive"))
      (node (ref "USB1") (pin "A5") (pinfunction "CC1_A5") (pintype "bidirectional"))
    )
    (net (code "47") (name "Net-(USB1-CC2)") (class "Default")
      (node (ref "R12") (pin "1") (pinfunction "1_1") (pintype "passive"))
      (node (ref "USB1") (pin "B5") (pinfunction "CC2_B5") (pintype "bidirectional"))
    )
    (net (code "48") (name "QSPI_SCLK") (class "Default")
      (node (ref "IC1") (pin "52") (pinfunction "QSPI_SCLK_52") (pintype "bidirectional"))
      (node (ref "IC2") (pin "6") (pinfunction "CLK_6") (pintype "bidirectional"))
    )
    (net (code "49") (name "QSPI_SD0") (class "Default")
      (node (ref "IC1") (pin "53") (pinfunction "QSPI_SD0_53") (pintype "bidirectional"))
      (node (ref "IC2") (pin "5") (pinfunction "DI/IO0_5") (pintype "bidirectional"))
    )
    (net (code "50") (name "QSPI_SD1") (class "Default")
      (node (ref "IC1") (pin "55") (pinfunction "QSPI_SD1_55") (pintype "bidirectional"))
      (node (ref "IC2") (pin "2") (pinfunction "DO/IO1_2") (pintype "bidirectional"))
    )
    (net (code "51") (name "QSPI_SD2") (class "Default")
      (node (ref "IC1") (pin "54") (pinfunction "QSPI_SD2_54") (pintype "bidirectional"))
      (node (ref "IC2") (pin "3") (pinfunction "~{WP}/IO2_3") (pintype "bidirectional"))
    )
    (net (code "52") (name "QSPI_SD3") (class "Default")
      (node (ref "IC1") (pin "51") (pinfunction "QSPI_SD3_51") (pintype "bidirectional"))
      (node (ref "IC2") (pin "7") (pinfunction "~{HOLD}/IO3_7") (pintype "bidirectional"))
    )
    (net (code "53") (name "QSPI_SS") (class "Default")
      (node (ref "IC1") (pin "56") (pinfunction "QSPI_SS_N_56") (pintype "bidirectional"))
      (node (ref "IC2") (pin "1") (pinfunction "~{CS}_1") (pintype "bidirectional"))
      (node (ref "R5") (pin "2") (pinfunction "2_2") (pintype "passive"))
    )
    (net (code "54") (name "RESET") (class "Default")
      (node (ref "IC1") (pin "26") (pinfunction "RUN_26") (pintype "input"))
      (node (ref "PICO1") (pin "R") (pinfunction "RUN_R") (pintype "bidirectional"))
      (node (ref "PICO1") (pin "RUN") (pinfunction "RUN_RUN") (pintype "bidirectional"))
      (node (ref "R1") (pin "2") (pinfunction "2_2") (pintype "passive"))
      (node (ref "RESET") (pin "1") (pinfunction "P$1_1") (pintype "bidirectional"))
    )
    (net (code "55") (name "SWCLK") (class "Default")
      (node (ref "IC1") (pin "24") (pinfunction "SWCLK_24") (pintype "input"))
      (node (ref "PICO1") (pin "SWC") (pinfunction "SWCLK_SWC") (pintype "bidirectional"))
      (node (ref "PICO1") (pin "SWCLK") (pinfunction "SWCLK_SWCLK") (pintype "bidirectional"))
    )
    (net (code "56") (name "SWDIO") (class "Default")
      (node (ref "IC1") (pin "25") (pinfunction "SWDIO_25") (pintype "bidirectional"))
      (node (ref "PICO1") (pin "SWD") (pinfunction "SWDIO_SWD") (pintype "bidirectional"))
      (node (ref "PICO1") (pin "SWDIO") (pinfunction "SWDIO_SWDIO") (pintype "bidirectional"))
    )
    (net (code "57") (name "USB_DP_N") (class "Default")
      (node (ref "ESD1") (pin "3") (pinfunction "C2_3") (pintype "bidirectional"))
      (node (ref "R2") (pin "2") (pinfunction "2_2") (pintype "passive"))
      (node (ref "TP2") (pin "TP") (pinfunction "TP_TP") (pintype "input"))
      (node (ref "USB1") (pin "A7") (pinfunction "D-_A7") (pintype "bidirectional"))
      (node (ref "USB1") (pin "B7") (pinfunction "D-_B7") (pintype "bidirectional"))
    )
    (net (code "58") (name "USB_DP_P") (class "Default")
      (node (ref "ESD1") (pin "2") (pinfunction "C1_2") (pintype "bidirectional"))
      (node (ref "R3") (pin "2") (pinfunction "2_2") (pintype "passive"))
      (node (ref "TP3") (pin "TP") (pinfunction "TP_TP") (pintype "input"))
      (node (ref "USB1") (pin "A6") (pinfunction "D+_A6") (pintype "bidirectional"))
      (node (ref "USB1") (pin "B6") (pinfunction "D+_B6") (pintype "bidirectional"))
    )
    (net (code "59") (name "USB_RDP_N") (class "Default")
      (node (ref "IC1") (pin "46") (pinfunction "USB_DM_46") (pintype "bidirectional"))
      (node (ref "R2") (pin "1") (pinfunction "1_1") (pintype "passive"))
    )
    (net (code "60") (name "USB_RDP_P") (class "Default")
      (node (ref "IC1") (pin "47") (pinfunction "USB_DP_47") (pintype "bidirectional"))
      (node (ref "R3") (pin "1") (pinfunction "1_1") (pintype "passive"))
    )
    (net (code "61") (name "VBUS") (class "Default")
      (node (ref "D1") (pin "A") (pinfunction "A_A") (pintype "passive"))
      (node (ref "ESD1") (pin "4") (pinfunction "C3_4") (pintype "bidirectional"))
      (node (ref "PICO1") (pin "VBU") (pinfunction "VBUS_VBU") (pintype "bidirectional"))
      (node (ref "PICO1") (pin "VBUS") (pinfunction "VBUS_VBUS") (pintype "bidirectional"))
      (node (ref "R16") (pin "1") (pinfunction "1_1") (pintype "passive"))
      (node (ref "USB1") (pin "VBUS1") (pinfunction "VBUS_VBUS1") (pintype "power_in"))
      (node (ref "USB1") (pin "VBUS2") (pinfunction "VBUS_VBUS2") (pintype "power_in"))
    )
    (net (code "62") (name "VCORE") (class "Default")
      (node (ref "C11") (pin "1") (pinfunction "1_1") (pintype "passive"))
      (node (ref "C12") (pin "1") (pinfunction "1_1") (pintype "passive"))
      (node (ref "IC1") (pin "23") (pinfunction "DVDD1_23") (pintype "power_in"))
      (node (ref "IC1") (pin "50") (pinfunction "DVDD2_50") (pintype "power_in"))
      (node (ref "J3") (pin "2") (pinfunction "2_2") (pintype "bidirectional"))
    )
    (net (code "63") (name "VCORE_EXT") (class "Default")
      (node (ref "C21") (pin "1") (pinfunction "1_1") (pintype "passive"))
      (node (ref "C31") (pin "1") (pinfunction "1_1") (pintype "passive"))
      (node (ref "IC8") (pin "5") (pinfunction "VOUT_5") (pintype "power_in"))
      (node (ref "J3") (pin "1") (pinfunction "1_1") (pintype "bidirectional"))
      (node (ref "R9") (pin "1") (pinfunction "1_1") (pintype "passive"))
    )
    (net (code "64") (name "VFB") (class "Default")
      (node (ref "IC8") (pin "4") (pinfunction "FB_4") (pintype "input"))
      (node (ref "R10") (pin "1") (pinfunction "1_1") (pintype "passive"))
      (node (ref "R9") (pin "2") (pinfunction "2_2") (pintype "passive"))
    )
    (net (code "65") (name "VREF") (class "Default")
      (node (ref "C17") (pin "1") (pinfunction "1_1") (pintype "passive"))
      (node (ref "C32") (pin "1") (pinfunction "1_1") (pintype "passive"))
      (node (ref "IC5") (pin "3") (pinfunction "+IN_3") (pintype "input"))
      (node (ref "R6") (pin "2") (pinfunction "2_2") (pintype "passive"))
      (node (ref "REF1") (pin "1") (pinfunction "C_1") (pintype "passive"))
    )
    (net (code "66") (name "VREGO") (class "Default")
      (node (ref "C10") (pin "1") (pinfunction "1_1") (pintype "passive"))
      (node (ref "C9") (pin "1") (pinfunction "1_1") (pintype "passive"))
      (node (ref "IC1") (pin "45") (pinfunction "VREG_VOUT_45") (pintype "power_in"))
      (node (ref "J3") (pin "3") (pinfunction "3_3") (pintype "bidirectional"))
    )
    (net (code "67") (name "V_SYS") (class "Default")
      (node (ref "C23") (pin "1") (pinfunction "1_1") (pintype "passive"))
      (node (ref "C25") (pin "1") (pinfunction "1_1") (pintype "passive"))
      (node (ref "D1") (pin "C") (pinfunction "C_C") (pintype "passive"))
      (node (ref "IC3") (pin "1") (pinfunction "VIN_1") (pintype "bidirectional"))
      (node (ref "PICO1") (pin "VSY") (pinfunction "VSYS_VSY") (pintype "bidirectional"))
      (node (ref "PICO1") (pin "VSYS") (pinfunction "VSYS_VSYS") (pintype "bidirectional"))
      (node (ref "R15") (pin "1") (pinfunction "1_1") (pintype "passive"))
      (node (ref "R19") (pin "1") (pinfunction "1_1") (pintype "passive"))
    )
    (net (code "68") (name "XIN") (class "Default")
      (node (ref "C15") (pin "1") (pinfunction "1_1") (pintype "passive"))
      (node (ref "IC1") (pin "20") (pinfunction "XIN_20") (pintype "input"))
      (node (ref "X1") (pin "3") (pinfunction "2_3") (pintype "passive"))
    )
    (net (code "69") (name "XOUT") (class "Default")
      (node (ref "IC1") (pin "21") (pinfunction "XOUT_21") (pintype "output"))
      (node (ref "R4") (pin "1") (pinfunction "1_1") (pintype "passive"))
    )
    (net (code "70") (name "unconnected-(IC3-NC-Pad4)") (class "Default")
      (node (ref "IC3") (pin "4") (pinfunction "NC_4") (pintype "bidirectional"))
    )
    (net (code "71") (name "unconnected-(USB1-SBU1-PadA8)") (class "Default")
      (node (ref "USB1") (pin "A8") (pinfunction "SBU1_A8") (pintype "bidirectional"))
    )
    (net (code "72") (name "unconnected-(USB1-SBU2-PadB8)") (class "Default")
      (node (ref "USB1") (pin "B8") (pinfunction "SBU2_B8") (pintype "bidirectional"))
    )
  )
)
